# Motor_Driver_Unit.net
KiCad netlist of a schematic drawn in Altium Designer
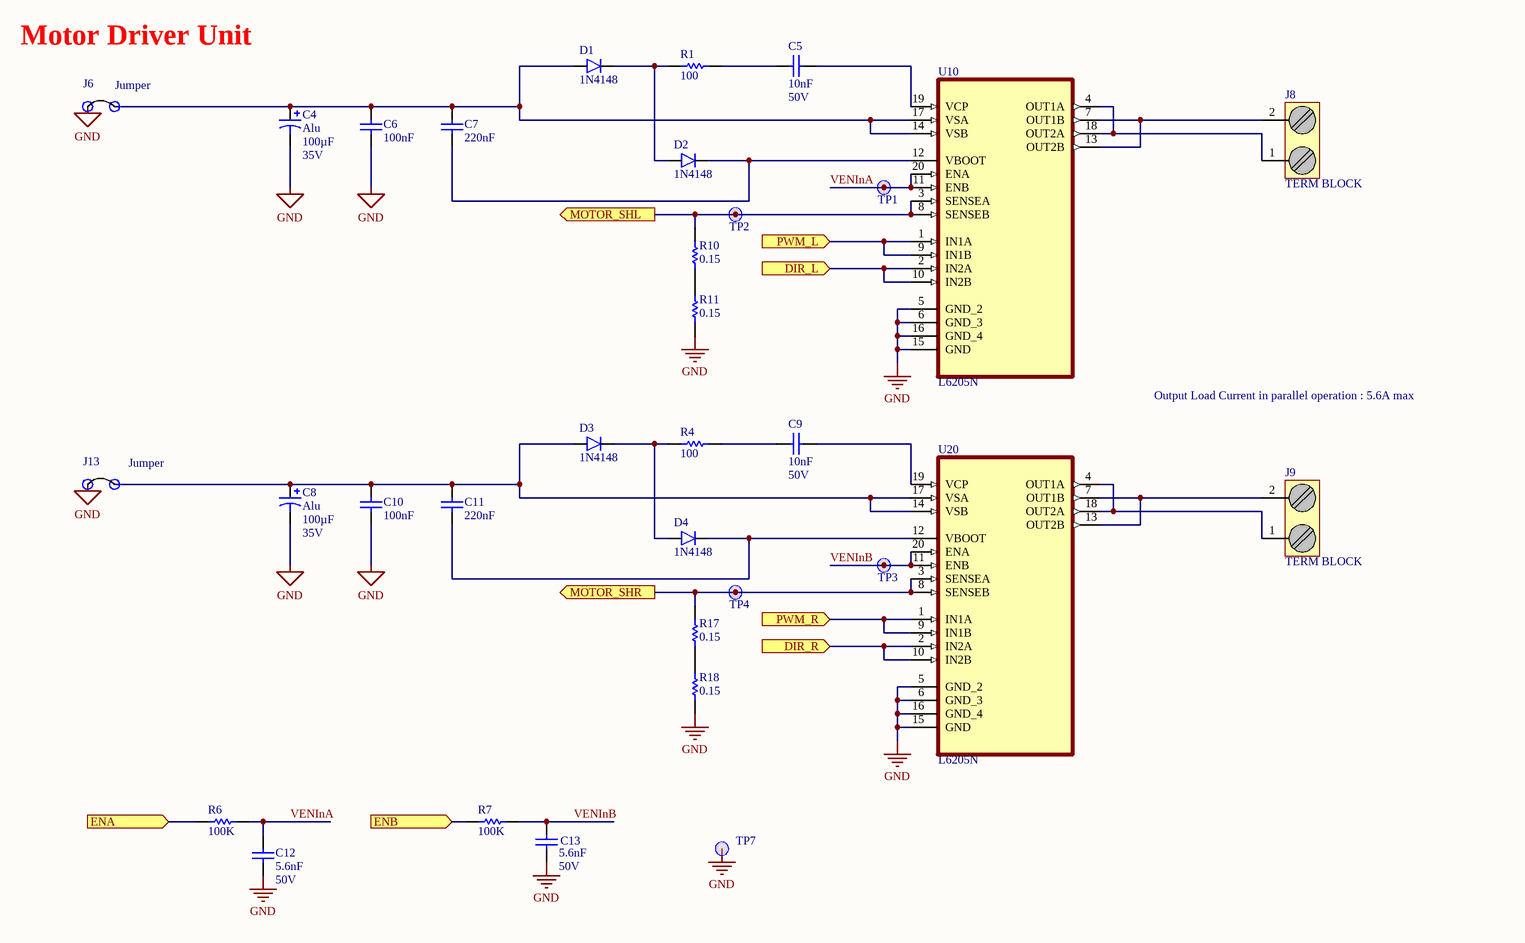
[diagram p0: Motor Driver Unit.SchDoc]

(export (version "E")
  (design (tool "Eeschema 10.0.6"))
  (components
    (comp (ref "C4")
      (value "Alu")
      (footprint "UWT1V101MCL1GS")
      (description "CAP ALUM 100UF 20% 35V SMD")
      (fields
        (field (name "MANUFACTURER") "Nichicon")
        (field (name "PART NUMBER") "UWT1V101MCL1GS")
        (field (name "CAPACITANCE") "100µF")
        (field (name "VOLTAGE") "35V")
      )
      (libsource (lib "Nichicon") (part "UWT1V101MCL1GS"))
    )
    (comp (ref "C5")
      (value "10nF")
      (footprint "CAP-SMT:CC0603 x 0.90mm")
      (description "10000pF ±10% 50V Ceramic Capacitor X7R 0603 (1608 Metric)")
      (fields
        (field (name "MANUFACTURER") "Yageo")
        (field (name "PART NUMBER") "CC0603KRX7R9BB103")
        (field (name "VOLTAGE - RATED") "50V")
      )
      (libsource (lib "MLCC") (part "CAP"))
    )
    (comp (ref "C6")
      (value "100nF")
      (footprint "CAP-SMT:CC0805 x 0.90mm")
      (fields (field (name "Comment") "CAP"))
      (libsource (lib "MLCC") (part "CAP"))
    )
    (comp (ref "C7")
      (value "220nF")
      (footprint "CAP-SMT:CC0805 x 0.90mm")
      (fields (field (name "Comment") "CAP"))
      (libsource (lib "MLCC") (part "CAP"))
    )
    (comp (ref "C8")
      (value "Alu")
      (footprint "UWT1V101MCL1GS")
      (description "CAP ALUM 100UF 20% 35V SMD")
      (fields
        (field (name "MANUFACTURER") "Nichicon")
        (field (name "PART NUMBER") "UWT1V101MCL1GS")
        (field (name "CAPACITANCE") "100µF")
        (field (name "VOLTAGE") "35V")
      )
      (libsource (lib "Nichicon") (part "UWT1V101MCL1GS"))
    )
    (comp (ref "C9")
      (value "10nF")
      (footprint "CAP-SMT:CC0603 x 0.90mm")
      (description "10000pF ±10% 50V Ceramic Capacitor X7R 0603 (1608 Metric)")
      (fields
        (field (name "MANUFACTURER") "Yageo")
        (field (name "PART NUMBER") "CC0603KRX7R9BB103")
        (field (name "VOLTAGE - RATED") "50V")
      )
      (libsource (lib "MLCC") (part "CAP"))
    )
    (comp (ref "C10")
      (value "100nF")
      (footprint "CAP-SMT:CC0805 x 0.90mm")
      (fields (field (name "Comment") "CAP"))
      (libsource (lib "MLCC") (part "CAP"))
    )
    (comp (ref "C11")
      (value "220nF")
      (footprint "CAP-SMT:CC0603 x 0.9mm")
      (fields (field (name "Comment") "CAP"))
      (libsource (lib "MLCC") (part "CAP"))
    )
    (comp (ref "C12")
      (value "5.6nF")
      (footprint "CC0603 x 0.90mm")
      (description "5600pF ±5% 50V Ceramic Capacitor X7R 0603 (1608 Metric)")
      (fields
        (field (name "MANUFACTURER") "Yageo")
        (field (name "PART NUMBER") "CC0603JRX7R9BB562")
        (field (name "VOLTAGE - RATED") "50V")
      )
      (libsource (lib "MLCC") (part "CAP"))
    )
    (comp (ref "C13")
      (value "5.6nF")
      (footprint "CAP-SMT:CC0603 x 0.90mm")
      (description "5600pF ±5% 50V Ceramic Capacitor X7R 0603 (1608 Metric)")
      (fields
        (field (name "MANUFACTURER") "Yageo")
        (field (name "PART NUMBER") "CC0603JRX7R9BB562")
        (field (name "VOLTAGE - RATED") "50V")
      )
      (libsource (lib "MLCC") (part "CAP"))
    )
    (comp (ref "D1")
      (value "1N4148")
      (footprint "SOD323")
      (description "75V 300mA SURFACE MOUNT FAST SWITCHING DIODE")
      (fields (field (name "PART NUMBER") "1N4148WS-7-F") (field (name "MANUFACTURER") "Diodes Inc."))
      (libsource (lib "Diodes Inc") (part "1N4148WS-7-F"))
    )
    (comp (ref "D2")
      (value "1N4148")
      (footprint "SOD323")
      (description "75V 300mA SURFACE MOUNT FAST SWITCHING DIODE")
      (fields (field (name "PART NUMBER") "1N4148WS-7-F") (field (name "MANUFACTURER") "Diodes Inc."))
      (libsource (lib "Diodes Inc") (part "1N4148WS-7-F"))
    )
    (comp (ref "D3")
      (value "1N4148")
      (footprint "SOD323")
      (description "75V 300mA SURFACE MOUNT FAST SWITCHING DIODE")
      (fields (field (name "PART NUMBER") "1N4148WS-7-F") (field (name "MANUFACTURER") "Diodes Inc."))
      (libsource (lib "Diodes Inc") (part "1N4148WS-7-F"))
    )
    (comp (ref "D4")
      (value "1N4148")
      (footprint "SOD323")
      (description "75V 300mA SURFACE MOUNT FAST SWITCHING DIODE")
      (fields (field (name "PART NUMBER") "1N4148WS-7-F") (field (name "MANUFACTURER") "Diodes Inc."))
      (libsource (lib "Diodes Inc") (part "1N4148WS-7-F"))
    )
    (comp (ref "J6")
      (value "Jumper")
      (footprint "68002-102HLF")
      (description "JUMPER Headers 2POS 2.54mm pitch for jumper")
      (fields (field (name "MANUFACTURER") "Amphenol FCI") (field (name "PART NUMBER") "68002-102HLF"))
      (libsource (lib "Amphenol") (part "68002-102HLF JMP"))
    )
    (comp (ref "J8")
      (value "TERM BLOCK")
      (footprint "282841-2")
      (description "TERM BLOCK 2POS SIDE ENT 5.08MM")
      (fields (field (name "PART NUMBER") "282841-2") (field (name "MANUFACTURER") "TE Connectivity"))
      (libsource (lib "TE-Connectivity") (part "282841-2"))
    )
    (comp (ref "J9")
      (value "TERM BLOCK")
      (footprint "282841-2")
      (description "TERM BLOCK 2POS SIDE ENT 5.08MM")
      (fields (field (name "PART NUMBER") "282841-2") (field (name "MANUFACTURER") "TE Connectivity"))
      (libsource (lib "TE-Connectivity") (part "282841-2"))
    )
    (comp (ref "J13")
      (value "Jumper")
      (footprint "68002-102HLF")
      (description "JUMPER Headers 2POS 2.54mm pitch for jumper")
      (fields (field (name "MANUFACTURER") "Amphenol FCI") (field (name "PART NUMBER") "68002-102HLF"))
      (libsource (lib "Amphenol") (part "68002-102HLF JMP"))
    )
    (comp (ref "R1")
      (value "100")
      (footprint "RES-SMT:RESC0603_N")
      (description "RES 100 OHM 1/10W 1% 0603 SMD")
      (fields (field (name "PART NUMBER") "9C06031A1000FKHFT") (field (name "MANUFACTURER") "Yageo"))
      (libsource (lib "RES-SMT") (part "RES"))
    )
    (comp (ref "R4")
      (value "100")
      (footprint "RES-SMT:RESC0603_N")
      (description "RES 100 OHM 1/10W 1% 0603 SMD")
      (fields (field (name "PART NUMBER") "9C06031A1000FKHFT") (field (name "MANUFACTURER") "Yageo"))
      (libsource (lib "RES-SMT") (part "RES"))
    )
    (comp (ref "R6")
      (value "100K")
      (footprint "RESC0603_N")
      (description "RES 100K OHM 1/10W .5% SMD 0603")
      (fields (field (name "PART NUMBER") "RT0603DRE07100KL") (field (name "MANUFACTURER") "Yageo"))
      (libsource (lib "RES-SMT") (part "RES"))
    )
    (comp (ref "R7")
      (value "100K")
      (footprint "RESC0603_N")
      (description "RES 100K OHM 1/10W .5% SMD 0603")
      (fields (field (name "PART NUMBER") "RT0603DRE07100KL") (field (name "MANUFACTURER") "Yageo"))
      (libsource (lib "RES-SMT") (part "RES"))
    )
    (comp (ref "R10")
      (value "0.15")
      (footprint "RESC0603_N")
      (description "RES .15 OHM 1/10W 1% 0603 SMD")
      (fields (field (name "PART NUMBER") "RL0603FR-070R15L") (field (name "MANUFACTURER") "Yageo"))
      (libsource (lib "RES-SMT") (part "RES"))
    )
    (comp (ref "R11")
      (value "0.15")
      (footprint "RESC0603_N")
      (description "RES .15 OHM 1/10W 1% 0603 SMD")
      (fields (field (name "PART NUMBER") "RL0603FR-070R15L") (field (name "MANUFACTURER") "Yageo"))
      (libsource (lib "RES-SMT") (part "RES"))
    )
    (comp (ref "R17")
      (value "0.15")
      (footprint "RESC0603_N")
      (description "RES .15 OHM 1/10W 1% 0603 SMD")
      (fields (field (name "PART NUMBER") "RL0603FR-070R15L") (field (name "MANUFACTURER") "Yageo"))
      (libsource (lib "RES-SMT") (part "RES"))
    )
    (comp (ref "R18")
      (value "0.15")
      (footprint "RESC0603_N")
      (description "RES .15 OHM 1/10W 1% 0603 SMD")
      (fields (field (name "PART NUMBER") "RL0603FR-070R15L") (field (name "MANUFACTURER") "Yageo"))
      (libsource (lib "RES-SMT") (part "RES"))
    )
    (comp (ref "TP1")
      (value "TEST_POINT_1.27mm")
      (footprint "Test_Point1.27mm")
      (libsource (lib "avnet") (part "TEST_POINT_1.27mm"))
    )
    (comp (ref "TP2")
      (value "TEST_POINT_1.27mm")
      (footprint "Test_Point1.27mm")
      (libsource (lib "avnet") (part "TEST_POINT_1.27mm"))
    )
    (comp (ref "TP3")
      (value "TEST_POINT_1.27mm")
      (footprint "Test_Point1.27mm")
      (libsource (lib "avnet") (part "TEST_POINT_1.27mm"))
    )
    (comp (ref "TP4")
      (value "TEST_POINT_1.27mm")
      (footprint "Test_Point1.27mm")
      (libsource (lib "avnet") (part "TEST_POINT_1.27mm"))
    )
    (comp (ref "TP7")
      (value "TEST_POINT_1.27mm")
      (footprint "Test_Point1.27mm")
      (libsource (lib "avnet") (part "TEST_POINT_1.27mm"))
    )
    (comp (ref "U10")
      (value "L6205N")
      (footprint "DIP254P762X510-20")
      (description "L6205N DIP Half H-Bridge Driver _Internal FET_ Power Management Evaluation Board")
      (fields (field (name "MF") "STMicroelectronics"))
      (libsource (lib "L6205N") (part "L6205N"))
    )
    (comp (ref "U20")
      (value "L6205N")
      (footprint "DIP254P762X510-20")
      (description "L6205N DIP Half H-Bridge Driver _Internal FET_ Power Management Evaluation Board")
      (fields (field (name "MF") "STMicroelectronics"))
      (libsource (lib "L6205N") (part "L6205N"))
    )
  )
  (nets
    (net (code "1") (name "/DIR_L") (class "Default")
      (node (ref "U10") (pin "10") (pinfunction "IN2B_10") (pintype "input"))
      (node (ref "U10") (pin "2") (pinfunction "IN2A_2") (pintype "input"))
    )
    (net (code "2") (name "/DIR_R") (class "Default")
      (node (ref "U20") (pin "10") (pinfunction "IN2B_10") (pintype "input"))
      (node (ref "U20") (pin "2") (pinfunction "IN2A_2") (pintype "input"))
    )
    (net (code "3") (name "/ENA") (class "Default")
      (node (ref "R6") (pin "2") (pinfunction "2_2") (pintype "passive"))
    )
    (net (code "4") (name "/ENB") (class "Default")
      (node (ref "R7") (pin "2") (pinfunction "2_2") (pintype "passive"))
    )
    (net (code "5") (name "/MOTOR_SHL") (class "Default")
      (node (ref "R10") (pin "2") (pinfunction "2_2") (pintype "passive"))
      (node (ref "TP2") (pin "1") (pinfunction "1_1") (pintype "passive"))
      (node (ref "U10") (pin "3") (pinfunction "SENSEA_3") (pintype "input"))
      (node (ref "U10") (pin "8") (pinfunction "SENSEB_8") (pintype "input"))
    )
    (net (code "6") (name "/MOTOR_SHR") (class "Default")
      (node (ref "R17") (pin "2") (pinfunction "2_2") (pintype "passive"))
      (node (ref "TP4") (pin "1") (pinfunction "1_1") (pintype "passive"))
      (node (ref "U20") (pin "3") (pinfunction "SENSEA_3") (pintype "input"))
      (node (ref "U20") (pin "8") (pinfunction "SENSEB_8") (pintype "input"))
    )
    (net (code "7") (name "/PWM_L") (class "Default")
      (node (ref "U10") (pin "1") (pinfunction "IN1A_1") (pintype "input"))
      (node (ref "U10") (pin "9") (pinfunction "IN1B_9") (pintype "input"))
    )
    (net (code "8") (name "/PWM_R") (class "Default")
      (node (ref "U20") (pin "1") (pinfunction "IN1A_1") (pintype "input"))
      (node (ref "U20") (pin "9") (pinfunction "IN1B_9") (pintype "input"))
    )
    (net (code "9") (name "/VENInA") (class "Default")
      (node (ref "C12") (pin "2") (pinfunction "2_2") (pintype "passive"))
      (node (ref "R6") (pin "1") (pinfunction "1_1") (pintype "passive"))
      (node (ref "TP1") (pin "1") (pinfunction "1_1") (pintype "passive"))
      (node (ref "U10") (pin "11") (pinfunction "ENB_11") (pintype "input"))
      (node (ref "U10") (pin "20") (pinfunction "ENA_20") (pintype "input"))
    )
    (net (code "10") (name "/VENInB") (class "Default")
      (node (ref "C13") (pin "2") (pinfunction "2_2") (pintype "passive"))
      (node (ref "R7") (pin "1") (pinfunction "1_1") (pintype "passive"))
      (node (ref "TP3") (pin "1") (pinfunction "1_1") (pintype "passive"))
      (node (ref "U20") (pin "11") (pinfunction "ENB_11") (pintype "input"))
      (node (ref "U20") (pin "20") (pinfunction "ENA_20") (pintype "input"))
    )
    (net (code "11") (name "GND") (class "Default")
      (node (ref "C10") (pin "1") (pinfunction "1_1") (pintype "passive"))
      (node (ref "C12") (pin "1") (pinfunction "1_1") (pintype "passive"))
      (node (ref "C13") (pin "1") (pinfunction "1_1") (pintype "passive"))
      (node (ref "C4") (pin "2") (pinfunction "2_2") (pintype "passive"))
      (node (ref "C6") (pin "1") (pinfunction "1_1") (pintype "passive"))
      (node (ref "C8") (pin "2") (pinfunction "2_2") (pintype "passive"))
      (node (ref "J13") (pin "1") (pinfunction "1_1") (pintype "passive"))
      (node (ref "J6") (pin "1") (pinfunction "1_1") (pintype "passive"))
      (node (ref "R11") (pin "1") (pinfunction "1_1") (pintype "passive"))
      (node (ref "R18") (pin "1") (pinfunction "1_1") (pintype "passive"))
      (node (ref "TP7") (pin "1") (pinfunction "1_1") (pintype "passive"))
      (node (ref "U10") (pin "15") (pinfunction "GND_15") (pintype "passive"))
      (node (ref "U10") (pin "16") (pinfunction "GND_4_16") (pintype "passive"))
      (node (ref "U10") (pin "5") (pinfunction "GND_2_5") (pintype "passive"))
      (node (ref "U10") (pin "6") (pinfunction "GND_3_6") (pintype "passive"))
      (node (ref "U20") (pin "15") (pinfunction "GND_15") (pintype "passive"))
      (node (ref "U20") (pin "16") (pinfunction "GND_4_16") (pintype "passive"))
      (node (ref "U20") (pin "5") (pinfunction "GND_2_5") (pintype "passive"))
      (node (ref "U20") (pin "6") (pinfunction "GND_3_6") (pintype "passive"))
    )
    (net (code "12") (name "Net-(C5-Pad1)") (class "Default")
      (node (ref "C5") (pin "1") (pinfunction "1_1") (pintype "passive"))
      (node (ref "R1") (pin "2") (pinfunction "2_2") (pintype "passive"))
    )
    (net (code "13") (name "Net-(C9-Pad1)") (class "Default")
      (node (ref "C9") (pin "1") (pinfunction "1_1") (pintype "passive"))
      (node (ref "R4") (pin "2") (pinfunction "2_2") (pintype "passive"))
    )
    (net (code "14") (name "Net-(D1-A)") (class "Default")
      (node (ref "C4") (pin "1") (pinfunction "1_1") (pintype "passive"))
      (node (ref "C6") (pin "2") (pinfunction "2_2") (pintype "passive"))
      (node (ref "C7") (pin "2") (pinfunction "2_2") (pintype "passive"))
      (node (ref "D1") (pin "1") (pinfunction "A_1") (pintype "passive"))
      (node (ref "J6") (pin "2") (pinfunction "2_2") (pintype "passive"))
      (node (ref "U10") (pin "14") (pinfunction "VSB_14") (pintype "input"))
      (node (ref "U10") (pin "17") (pinfunction "VSA_17") (pintype "input"))
    )
    (net (code "15") (name "Net-(D1-K)") (class "Default")
      (node (ref "D1") (pin "2") (pinfunction "K_2") (pintype "passive"))
      (node (ref "D2") (pin "1") (pinfunction "A_1") (pintype "passive"))
      (node (ref "R1") (pin "1") (pinfunction "1_1") (pintype "passive"))
    )
    (net (code "16") (name "Net-(D2-K)") (class "Default")
      (node (ref "C7") (pin "1") (pinfunction "1_1") (pintype "passive"))
      (node (ref "D2") (pin "2") (pinfunction "K_2") (pintype "passive"))
      (node (ref "U10") (pin "12") (pinfunction "VBOOT_12") (pintype "passive"))
    )
    (net (code "17") (name "Net-(D3-A)") (class "Default")
      (node (ref "C10") (pin "2") (pinfunction "2_2") (pintype "passive"))
      (node (ref "C11") (pin "2") (pinfunction "2_2") (pintype "passive"))
      (node (ref "C8") (pin "1") (pinfunction "1_1") (pintype "passive"))
      (node (ref "D3") (pin "1") (pinfunction "A_1") (pintype "passive"))
      (node (ref "J13") (pin "2") (pinfunction "2_2") (pintype "passive"))
      (node (ref "U20") (pin "14") (pinfunction "VSB_14") (pintype "input"))
      (node (ref "U20") (pin "17") (pinfunction "VSA_17") (pintype "input"))
    )
    (net (code "18") (name "Net-(D3-K)") (class "Default")
      (node (ref "D3") (pin "2") (pinfunction "K_2") (pintype "passive"))
      (node (ref "D4") (pin "1") (pinfunction "A_1") (pintype "passive"))
      (node (ref "R4") (pin "1") (pinfunction "1_1") (pintype "passive"))
    )
    (net (code "19") (name "Net-(D4-K)") (class "Default")
      (node (ref "C11") (pin "1") (pinfunction "1_1") (pintype "passive"))
      (node (ref "D4") (pin "2") (pinfunction "K_2") (pintype "passive"))
      (node (ref "U20") (pin "12") (pinfunction "VBOOT_12") (pintype "passive"))
    )
    (net (code "20") (name "Net-(R10-Pad1)") (class "Default")
      (node (ref "R10") (pin "1") (pinfunction "1_1") (pintype "passive"))
      (node (ref "R11") (pin "2") (pinfunction "2_2") (pintype "passive"))
    )
    (net (code "21") (name "Net-(R17-Pad1)") (class "Default")
      (node (ref "R17") (pin "1") (pinfunction "1_1") (pintype "passive"))
      (node (ref "R18") (pin "2") (pinfunction "2_2") (pintype "passive"))
    )
    (net (code "22") (name "Net-(U10-OUT1A)") (class "Default")
      (node (ref "J8") (pin "1") (pintype "passive"))
      (node (ref "U10") (pin "18") (pinfunction "OUT2A_18") (pintype "output"))
      (node (ref "U10") (pin "4") (pinfunction "OUT1A_4") (pintype "output"))
    )
    (net (code "23") (name "Net-(U10-OUT1B)") (class "Default")
      (node (ref "J8") (pin "2") (pintype "passive"))
      (node (ref "U10") (pin "13") (pinfunction "OUT2B_13") (pintype "output"))
      (node (ref "U10") (pin "7") (pinfunction "OUT1B_7") (pintype "output"))
    )
    (net (code "24") (name "Net-(U10-VCP)") (class "Default")
      (node (ref "C5") (pin "2") (pinfunction "2_2") (pintype "passive"))
      (node (ref "U10") (pin "19") (pinfunction "VCP_19") (pintype "input"))
    )
    (net (code "25") (name "Net-(U20-OUT1A)") (class "Default")
      (node (ref "J9") (pin "1") (pintype "passive"))
      (node (ref "U20") (pin "18") (pinfunction "OUT2A_18") (pintype "output"))
      (node (ref "U20") (pin "4") (pinfunction "OUT1A_4") (pintype "output"))
    )
    (net (code "26") (name "Net-(U20-OUT1B)") (class "Default")
      (node (ref "J9") (pin "2") (pintype "passive"))
      (node (ref "U20") (pin "13") (pinfunction "OUT2B_13") (pintype "output"))
      (node (ref "U20") (pin "7") (pinfunction "OUT1B_7") (pintype "output"))
    )
    (net (code "27") (name "Net-(U20-VCP)") (class "Default")
      (node (ref "C9") (pin "2") (pinfunction "2_2") (pintype "passive"))
      (node (ref "U20") (pin "19") (pinfunction "VCP_19") (pintype "input"))
    )
  )
)
